# EATremolo.net
KiCad netlist of a schematic drawn in EAGLE
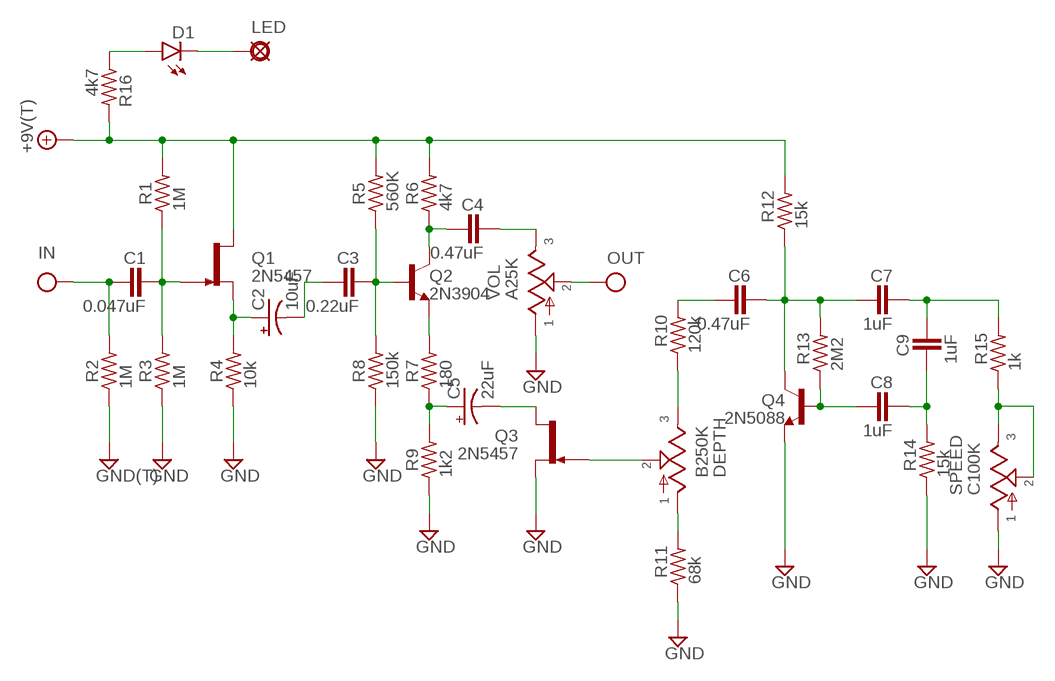
[diagram p0: schematic, sheet 1]

(export (version "E")
  (design (tool "Eeschema 10.0.6"))
  (components
    (comp (ref "+9V")
      (value "+9V(T)")
      (footprint "eagle-import:SQUARE")
      (libsource (lib "eagle-import") (part "+9V(T)"))
    )
    (comp (ref "C1")
      (value "0.047uF")
      (footprint "eagle-import:072X025")
      (libsource (lib "eagle-import") (part "072X0252"))
    )
    (comp (ref "C2")
      (value "10uF")
      (footprint "eagle-import:050_020_1")
      (libsource (lib "eagle-import") (part "0501"))
    )
    (comp (ref "C3")
      (value "0.22uF")
      (footprint "eagle-import:072X035")
      (libsource (lib "eagle-import") (part "072X0352"))
    )
    (comp (ref "C4")
      (value "0.47uF")
      (footprint "eagle-import:072X035")
      (libsource (lib "eagle-import") (part "072X0352"))
    )
    (comp (ref "C5")
      (value "22uF")
      (footprint "eagle-import:050_020_1")
      (libsource (lib "eagle-import") (part "0501"))
    )
    (comp (ref "C6")
      (value "0.47uF")
      (footprint "eagle-import:072X035")
      (libsource (lib "eagle-import") (part "072X0352"))
    )
    (comp (ref "C7")
      (value "1uF")
      (footprint "eagle-import:072X035")
      (libsource (lib "eagle-import") (part "072X0352"))
    )
    (comp (ref "C8")
      (value "1uF")
      (footprint "eagle-import:072X035")
      (libsource (lib "eagle-import") (part "072X0352"))
    )
    (comp (ref "C9")
      (value "1uF")
      (footprint "eagle-import:072X035")
      (libsource (lib "eagle-import") (part "072X0352"))
    )
    (comp (ref "D1")
      (value "LED3MM")
      (footprint "eagle-import:LED3MM")
      (libsource (lib "eagle-import") (part "LED3MM"))
    )
    (comp (ref "DEPTH")
      (value "B250K")
      (footprint "eagle-import:POT")
      (libsource (lib "eagle-import") (part "POT"))
    )
    (comp (ref "GND")
      (value "GND(T)")
      (footprint "eagle-import:SQUARE")
      (libsource (lib "eagle-import") (part "GND(T)"))
    )
    (comp (ref "IN")
      (value "IN(T)")
      (footprint "eagle-import:SQUARE")
      (libsource (lib "eagle-import") (part "IN(T)"))
    )
    (comp (ref "LED")
      (value "3mm")
      (footprint "eagle-import:SQUARE")
      (libsource (lib "eagle-import") (part "PAD"))
    )
    (comp (ref "OUT")
      (value "OUT(T)")
      (footprint "eagle-import:SQUARE")
      (libsource (lib "eagle-import") (part "OUT(T)"))
    )
    (comp (ref "Q1")
      (value "2N5457")
      (footprint "eagle-import:TO92-")
      (libsource (lib "eagle-import") (part "2N5457"))
    )
    (comp (ref "Q2")
      (value "2N3904")
      (footprint "eagle-import:TO92-")
      (libsource (lib "eagle-import") (part "2N3904"))
    )
    (comp (ref "Q3")
      (value "2N5457")
      (footprint "eagle-import:TO92-")
      (libsource (lib "eagle-import") (part "2N5457"))
    )
    (comp (ref "Q4")
      (value "2N5088")
      (footprint "eagle-import:TO92-")
      (libsource (lib "eagle-import") (part "2N5088"))
    )
    (comp (ref "R1")
      (value "1M")
      (footprint "eagle-import:R0207_3")
      (libsource (lib "eagle-import") (part "6MM.3"))
    )
    (comp (ref "R2")
      (value "1M")
      (footprint "eagle-import:R0207_3")
      (libsource (lib "eagle-import") (part "6MM.3"))
    )
    (comp (ref "R3")
      (value "1M")
      (footprint "eagle-import:R0207_3")
      (libsource (lib "eagle-import") (part "6MM.3"))
    )
    (comp (ref "R4")
      (value "10k")
      (footprint "eagle-import:R0207_3")
      (libsource (lib "eagle-import") (part "6MM.3"))
    )
    (comp (ref "R5")
      (value "560K")
      (footprint "eagle-import:R0207_3")
      (libsource (lib "eagle-import") (part "6MM.3"))
    )
    (comp (ref "R6")
      (value "4k7")
      (footprint "eagle-import:R0207_3")
      (libsource (lib "eagle-import") (part "6MM.3"))
    )
    (comp (ref "R7")
      (value "180")
      (footprint "eagle-import:R0207_3")
      (libsource (lib "eagle-import") (part "6MM.3"))
    )
    (comp (ref "R8")
      (value "150k")
      (footprint "eagle-import:R0207_3")
      (libsource (lib "eagle-import") (part "6MM.3"))
    )
    (comp (ref "R9")
      (value "1k2")
      (footprint "eagle-import:R0207_3")
      (libsource (lib "eagle-import") (part "6MM.3"))
    )
    (comp (ref "R10")
      (value "120k")
      (footprint "eagle-import:R0207_3")
      (libsource (lib "eagle-import") (part "6MM.3"))
    )
    (comp (ref "R11")
      (value "68k")
      (footprint "eagle-import:R0207_3")
      (libsource (lib "eagle-import") (part "6MM.3"))
    )
    (comp (ref "R12")
      (value "15k")
      (footprint "eagle-import:R0207_3")
      (libsource (lib "eagle-import") (part "6MM.3"))
    )
    (comp (ref "R13")
      (value "2M2")
      (footprint "eagle-import:R0207_3")
      (libsource (lib "eagle-import") (part "6MM.3"))
    )
    (comp (ref "R14")
      (value "15k")
      (footprint "eagle-import:R0207_3")
      (libsource (lib "eagle-import") (part "6MM.3"))
    )
    (comp (ref "R15")
      (value "1k")
      (footprint "eagle-import:R0207_3")
      (libsource (lib "eagle-import") (part "6MM.3"))
    )
    (comp (ref "R16")
      (value "4k7")
      (footprint "eagle-import:R0207_3")
      (libsource (lib "eagle-import") (part "6MM.3"))
    )
    (comp (ref "SPEED")
      (value "C100K")
      (footprint "eagle-import:POT")
      (libsource (lib "eagle-import") (part "POT"))
    )
    (comp (ref "VOL")
      (value "A25K")
      (footprint "eagle-import:POT")
      (libsource (lib "eagle-import") (part "POT"))
    )
  )
  (nets
    (net (code "1") (name "+9V(T)") (class "Default")
      (node (ref "+9V") (pin "1") (pinfunction "+9V_1") (pintype "power_in"))
      (node (ref "Q1") (pin "3") (pinfunction "D_3") (pintype "passive"))
      (node (ref "R1") (pin "2") (pinfunction "2_2") (pintype "passive"))
      (node (ref "R12") (pin "2") (pinfunction "2_2") (pintype "passive"))
      (node (ref "R16") (pin "2") (pinfunction "2_2") (pintype "passive"))
      (node (ref "R5") (pin "2") (pinfunction "2_2") (pintype "passive"))
      (node (ref "R6") (pin "2") (pinfunction "2_2") (pintype "passive"))
    )
    (net (code "2") (name "GND") (class "Default")
      (node (ref "GND") (pin "1") (pinfunction "GND_1") (pintype "power_in"))
      (node (ref "Q3") (pin "2") (pinfunction "S_2") (pintype "passive"))
      (node (ref "Q4") (pin "3") (pinfunction "E_3") (pintype "passive"))
      (node (ref "R11") (pin "1") (pinfunction "1_1") (pintype "passive"))
      (node (ref "R14") (pin "1") (pinfunction "1_1") (pintype "passive"))
      (node (ref "R2") (pin "1") (pinfunction "1_1") (pintype "passive"))
      (node (ref "R3") (pin "1") (pinfunction "1_1") (pintype "passive"))
      (node (ref "R4") (pin "1") (pinfunction "1_1") (pintype "passive"))
      (node (ref "R8") (pin "1") (pinfunction "1_1") (pintype "passive"))
      (node (ref "R9") (pin "1") (pinfunction "1_1") (pintype "passive"))
      (node (ref "SPEED") (pin "1") (pinfunction "1_1") (pintype "passive"))
      (node (ref "VOL") (pin "1") (pinfunction "1_1") (pintype "passive"))
    )
    (net (code "3") (name "IN(T)") (class "Default")
      (node (ref "C1") (pin "1") (pinfunction "1_1") (pintype "passive"))
      (node (ref "IN") (pin "1") (pinfunction "IN_1") (pintype "power_in"))
      (node (ref "R2") (pin "2") (pinfunction "2_2") (pintype "passive"))
    )
    (net (code "4") (name "Net-(C2-Pad-)") (class "Default")
      (node (ref "C2") (pin "-") (pinfunction "-_-") (pintype "passive"))
      (node (ref "C3") (pin "1") (pinfunction "1_1") (pintype "passive"))
    )
    (net (code "5") (name "Net-(C4-Pad2)") (class "Default")
      (node (ref "C4") (pin "2") (pinfunction "2_2") (pintype "passive"))
      (node (ref "VOL") (pin "3") (pinfunction "3_3") (pintype "passive"))
    )
    (net (code "6") (name "Net-(C5-Pad+)") (class "Default")
      (node (ref "C5") (pin "+") (pinfunction "+_+") (pintype "passive"))
      (node (ref "R7") (pin "1") (pinfunction "1_1") (pintype "passive"))
      (node (ref "R9") (pin "2") (pinfunction "2_2") (pintype "passive"))
    )
    (net (code "7") (name "Net-(C6-Pad1)") (class "Default")
      (node (ref "C6") (pin "1") (pinfunction "1_1") (pintype "passive"))
      (node (ref "R10") (pin "2") (pinfunction "2_2") (pintype "passive"))
    )
    (net (code "8") (name "Net-(C7-Pad2)") (class "Default")
      (node (ref "C7") (pin "2") (pinfunction "2_2") (pintype "passive"))
      (node (ref "C9") (pin "2") (pinfunction "2_2") (pintype "passive"))
      (node (ref "R15") (pin "2") (pinfunction "2_2") (pintype "passive"))
    )
    (net (code "9") (name "Net-(C8-Pad2)") (class "Default")
      (node (ref "C8") (pin "2") (pinfunction "2_2") (pintype "passive"))
      (node (ref "C9") (pin "1") (pinfunction "1_1") (pintype "passive"))
      (node (ref "R14") (pin "2") (pinfunction "2_2") (pintype "passive"))
    )
    (net (code "10") (name "Net-(D1-C)") (class "Default")
      (node (ref "D1") (pin "K") (pinfunction "C_K") (pintype "passive"))
      (node (ref "LED") (pin "1") (pinfunction "PAD_1") (pintype "passive"))
    )
    (net (code "11") (name "Net-(D1-PadA)") (class "Default")
      (node (ref "D1") (pin "A") (pinfunction "A_A") (pintype "passive"))
      (node (ref "R16") (pin "1") (pinfunction "1_1") (pintype "passive"))
    )
    (net (code "12") (name "Net-(DEPTH-Pad1)") (class "Default")
      (node (ref "DEPTH") (pin "1") (pinfunction "1_1") (pintype "passive"))
      (node (ref "R11") (pin "2") (pinfunction "2_2") (pintype "passive"))
    )
    (net (code "13") (name "Net-(DEPTH-Pad3)") (class "Default")
      (node (ref "DEPTH") (pin "3") (pinfunction "3_3") (pintype "passive"))
      (node (ref "R10") (pin "1") (pinfunction "1_1") (pintype "passive"))
    )
    (net (code "14") (name "Net-(Q1-G)") (class "Default")
      (node (ref "C1") (pin "2") (pinfunction "2_2") (pintype "passive"))
      (node (ref "Q1") (pin "1") (pinfunction "G_1") (pintype "passive"))
      (node (ref "R1") (pin "1") (pinfunction "1_1") (pintype "passive"))
      (node (ref "R3") (pin "2") (pinfunction "2_2") (pintype "passive"))
    )
    (net (code "15") (name "Net-(Q1-S)") (class "Default")
      (node (ref "C2") (pin "+") (pinfunction "+_+") (pintype "passive"))
      (node (ref "Q1") (pin "2") (pinfunction "S_2") (pintype "passive"))
      (node (ref "R4") (pin "2") (pinfunction "2_2") (pintype "passive"))
    )
    (net (code "16") (name "Net-(Q2-B)") (class "Default")
      (node (ref "C3") (pin "2") (pinfunction "2_2") (pintype "passive"))
      (node (ref "Q2") (pin "2") (pinfunction "B_2") (pintype "passive"))
      (node (ref "R5") (pin "1") (pinfunction "1_1") (pintype "passive"))
      (node (ref "R8") (pin "2") (pinfunction "2_2") (pintype "passive"))
    )
    (net (code "17") (name "Net-(Q2-C)") (class "Default")
      (node (ref "C4") (pin "1") (pinfunction "1_1") (pintype "passive"))
      (node (ref "Q2") (pin "1") (pinfunction "C_1") (pintype "passive"))
      (node (ref "R6") (pin "1") (pinfunction "1_1") (pintype "passive"))
    )
    (net (code "18") (name "Net-(Q2-E)") (class "Default")
      (node (ref "Q2") (pin "3") (pinfunction "E_3") (pintype "passive"))
      (node (ref "R7") (pin "2") (pinfunction "2_2") (pintype "passive"))
    )
    (net (code "19") (name "Net-(Q3-D)") (class "Default")
      (node (ref "C5") (pin "-") (pinfunction "-_-") (pintype "passive"))
      (node (ref "Q3") (pin "3") (pinfunction "D_3") (pintype "passive"))
    )
    (net (code "20") (name "Net-(Q3-G)") (class "Default")
      (node (ref "DEPTH") (pin "2") (pinfunction "2_2") (pintype "passive"))
      (node (ref "Q3") (pin "1") (pinfunction "G_1") (pintype "passive"))
    )
    (net (code "21") (name "Net-(Q4-B)") (class "Default")
      (node (ref "C8") (pin "1") (pinfunction "1_1") (pintype "passive"))
      (node (ref "Q4") (pin "2") (pinfunction "B_2") (pintype "passive"))
      (node (ref "R13") (pin "1") (pinfunction "1_1") (pintype "passive"))
    )
    (net (code "22") (name "Net-(Q4-C)") (class "Default")
      (node (ref "C6") (pin "2") (pinfunction "2_2") (pintype "passive"))
      (node (ref "C7") (pin "1") (pinfunction "1_1") (pintype "passive"))
      (node (ref "Q4") (pin "1") (pinfunction "C_1") (pintype "passive"))
      (node (ref "R12") (pin "1") (pinfunction "1_1") (pintype "passive"))
      (node (ref "R13") (pin "2") (pinfunction "2_2") (pintype "passive"))
    )
    (net (code "23") (name "Net-(R15-Pad1)") (class "Default")
      (node (ref "R15") (pin "1") (pinfunction "1_1") (pintype "passive"))
      (node (ref "SPEED") (pin "2") (pinfunction "2_2") (pintype "passive"))
      (node (ref "SPEED") (pin "3") (pinfunction "3_3") (pintype "passive"))
    )
    (net (code "24") (name "OUT(T)") (class "Default")
      (node (ref "OUT") (pin "1") (pinfunction "OUT_1") (pintype "power_in"))
      (node (ref "VOL") (pin "2") (pinfunction "2_2") (pintype "passive"))
    )
  )
)
